# main.net
KiCad netlist of a schematic drawn in Altium Designer
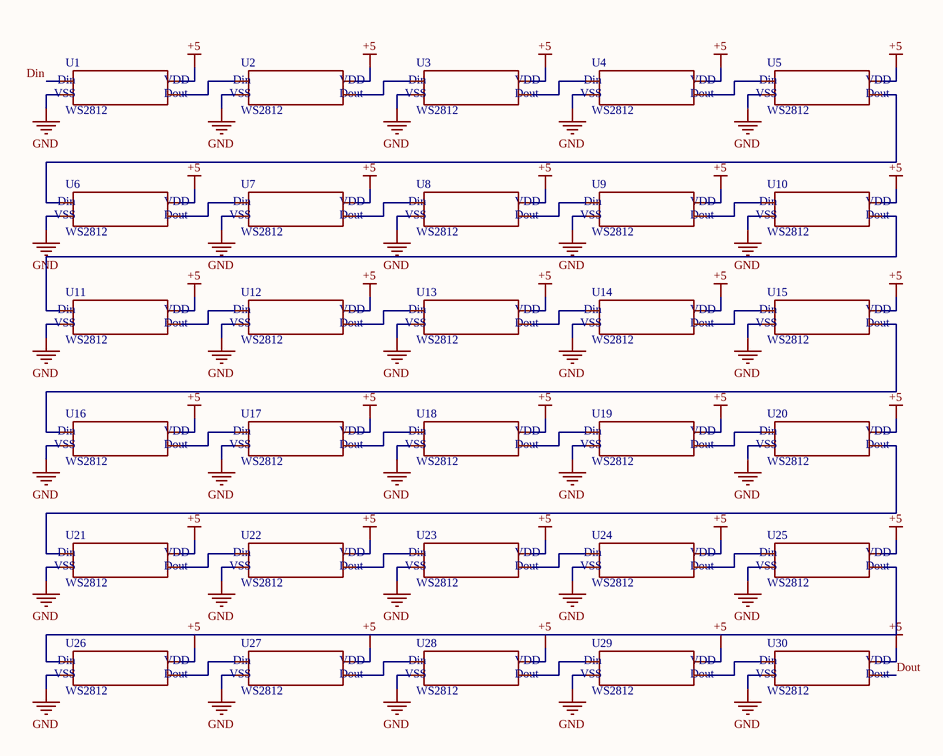
[diagram p0: main.SchDoc]

(export (version "E")
  (design (tool "Eeschema 10.0.6"))
  (components
    (comp (ref "U1") (value "WS2812") (footprint "3535") (libsource (lib "元件库") (part "芯片/IC-WS2812")))
    (comp (ref "U2") (value "WS2812") (footprint "3535") (libsource (lib "元件库") (part "芯片/IC-WS2812")))
    (comp (ref "U3") (value "WS2812") (footprint "3535") (libsource (lib "元件库") (part "芯片/IC-WS2812")))
    (comp (ref "U4") (value "WS2812") (footprint "3535") (libsource (lib "元件库") (part "芯片/IC-WS2812")))
    (comp (ref "U5") (value "WS2812") (footprint "3535") (libsource (lib "元件库") (part "芯片/IC-WS2812")))
    (comp (ref "U6") (value "WS2812") (footprint "3535") (libsource (lib "元件库") (part "芯片/IC-WS2812")))
    (comp (ref "U7") (value "WS2812") (footprint "3535") (libsource (lib "元件库") (part "芯片/IC-WS2812")))
    (comp (ref "U8") (value "WS2812") (footprint "3535") (libsource (lib "元件库") (part "芯片/IC-WS2812")))
    (comp (ref "U9") (value "WS2812") (footprint "3535") (libsource (lib "元件库") (part "芯片/IC-WS2812")))
    (comp (ref "U10") (value "WS2812") (footprint "3535") (libsource (lib "元件库") (part "芯片/IC-WS2812")))
    (comp (ref "U11") (value "WS2812") (footprint "3535") (libsource (lib "元件库") (part "芯片/IC-WS2812")))
    (comp (ref "U12") (value "WS2812") (footprint "3535") (libsource (lib "元件库") (part "芯片/IC-WS2812")))
    (comp (ref "U13") (value "WS2812") (footprint "3535") (libsource (lib "元件库") (part "芯片/IC-WS2812")))
    (comp (ref "U14") (value "WS2812") (footprint "3535") (libsource (lib "元件库") (part "芯片/IC-WS2812")))
    (comp (ref "U15") (value "WS2812") (footprint "3535") (libsource (lib "元件库") (part "芯片/IC-WS2812")))
    (comp (ref "U16") (value "WS2812") (footprint "3535") (libsource (lib "元件库") (part "芯片/IC-WS2812")))
    (comp (ref "U17") (value "WS2812") (footprint "3535") (libsource (lib "元件库") (part "芯片/IC-WS2812")))
    (comp (ref "U18") (value "WS2812") (footprint "3535") (libsource (lib "元件库") (part "芯片/IC-WS2812")))
    (comp (ref "U19") (value "WS2812") (footprint "3535") (libsource (lib "元件库") (part "芯片/IC-WS2812")))
    (comp (ref "U20") (value "WS2812") (footprint "3535") (libsource (lib "元件库") (part "芯片/IC-WS2812")))
    (comp (ref "U21") (value "WS2812") (footprint "3535") (libsource (lib "元件库") (part "芯片/IC-WS2812")))
    (comp (ref "U22") (value "WS2812") (footprint "3535") (libsource (lib "元件库") (part "芯片/IC-WS2812")))
    (comp (ref "U23") (value "WS2812") (footprint "3535") (libsource (lib "元件库") (part "芯片/IC-WS2812")))
    (comp (ref "U24") (value "WS2812") (footprint "3535") (libsource (lib "元件库") (part "芯片/IC-WS2812")))
    (comp (ref "U25") (value "WS2812") (footprint "3535") (libsource (lib "元件库") (part "芯片/IC-WS2812")))
    (comp (ref "U26") (value "WS2812") (footprint "3535") (libsource (lib "元件库") (part "芯片/IC-WS2812")))
    (comp (ref "U27") (value "WS2812") (footprint "3535") (libsource (lib "元件库") (part "芯片/IC-WS2812")))
    (comp (ref "U28") (value "WS2812") (footprint "3535") (libsource (lib "元件库") (part "芯片/IC-WS2812")))
    (comp (ref "U29") (value "WS2812") (footprint "3535") (libsource (lib "元件库") (part "芯片/IC-WS2812")))
    (comp (ref "U30") (value "WS2812") (footprint "3535") (libsource (lib "元件库") (part "芯片/IC-WS2812")))
  )
  (nets
    (net (code "1") (name "+5") (class "Default")
      (node (ref "U1") (pin "1") (pinfunction "1_1") (pintype "passive"))
      (node (ref "U10") (pin "1") (pinfunction "1_1") (pintype "passive"))
      (node (ref "U11") (pin "1") (pinfunction "1_1") (pintype "passive"))
      (node (ref "U12") (pin "1") (pinfunction "1_1") (pintype "passive"))
      (node (ref "U13") (pin "1") (pinfunction "1_1") (pintype "passive"))
      (node (ref "U14") (pin "1") (pinfunction "1_1") (pintype "passive"))
      (node (ref "U15") (pin "1") (pinfunction "1_1") (pintype "passive"))
      (node (ref "U16") (pin "1") (pinfunction "1_1") (pintype "passive"))
      (node (ref "U17") (pin "1") (pinfunction "1_1") (pintype "passive"))
      (node (ref "U18") (pin "1") (pinfunction "1_1") (pintype "passive"))
      (node (ref "U19") (pin "1") (pinfunction "1_1") (pintype "passive"))
      (node (ref "U2") (pin "1") (pinfunction "1_1") (pintype "passive"))
      (node (ref "U20") (pin "1") (pinfunction "1_1") (pintype "passive"))
      (node (ref "U21") (pin "1") (pinfunction "1_1") (pintype "passive"))
      (node (ref "U22") (pin "1") (pinfunction "1_1") (pintype "passive"))
      (node (ref "U23") (pin "1") (pinfunction "1_1") (pintype "passive"))
      (node (ref "U24") (pin "1") (pinfunction "1_1") (pintype "passive"))
      (node (ref "U25") (pin "1") (pinfunction "1_1") (pintype "passive"))
      (node (ref "U26") (pin "1") (pinfunction "1_1") (pintype "passive"))
      (node (ref "U27") (pin "1") (pinfunction "1_1") (pintype "passive"))
      (node (ref "U28") (pin "1") (pinfunction "1_1") (pintype "passive"))
      (node (ref "U29") (pin "1") (pinfunction "1_1") (pintype "passive"))
      (node (ref "U3") (pin "1") (pinfunction "1_1") (pintype "passive"))
      (node (ref "U30") (pin "1") (pinfunction "1_1") (pintype "passive"))
      (node (ref "U4") (pin "1") (pinfunction "1_1") (pintype "passive"))
      (node (ref "U5") (pin "1") (pinfunction "1_1") (pintype "passive"))
      (node (ref "U6") (pin "1") (pinfunction "1_1") (pintype "passive"))
      (node (ref "U7") (pin "1") (pinfunction "1_1") (pintype "passive"))
      (node (ref "U8") (pin "1") (pinfunction "1_1") (pintype "passive"))
      (node (ref "U9") (pin "1") (pinfunction "1_1") (pintype "passive"))
    )
    (net (code "2") (name "/Din") (class "Default")
      (node (ref "U1") (pin "4") (pinfunction "4_4") (pintype "passive"))
    )
    (net (code "3") (name "/Dout") (class "Default")
      (node (ref "U30") (pin "2") (pinfunction "2_2") (pintype "passive"))
    )
    (net (code "4") (name "GND") (class "Default")
      (node (ref "U1") (pin "3") (pinfunction "3_3") (pintype "passive"))
      (node (ref "U10") (pin "3") (pinfunction "3_3") (pintype "passive"))
      (node (ref "U11") (pin "3") (pinfunction "3_3") (pintype "passive"))
      (node (ref "U12") (pin "3") (pinfunction "3_3") (pintype "passive"))
      (node (ref "U13") (pin "3") (pinfunction "3_3") (pintype "passive"))
      (node (ref "U14") (pin "3") (pinfunction "3_3") (pintype "passive"))
      (node (ref "U15") (pin "3") (pinfunction "3_3") (pintype "passive"))
      (node (ref "U16") (pin "3") (pinfunction "3_3") (pintype "passive"))
      (node (ref "U17") (pin "3") (pinfunction "3_3") (pintype "passive"))
      (node (ref "U18") (pin "3") (pinfunction "3_3") (pintype "passive"))
      (node (ref "U19") (pin "3") (pinfunction "3_3") (pintype "passive"))
      (node (ref "U2") (pin "3") (pinfunction "3_3") (pintype "passive"))
      (node (ref "U20") (pin "3") (pinfunction "3_3") (pintype "passive"))
      (node (ref "U21") (pin "3") (pinfunction "3_3") (pintype "passive"))
      (node (ref "U22") (pin "3") (pinfunction "3_3") (pintype "passive"))
      (node (ref "U23") (pin "3") (pinfunction "3_3") (pintype "passive"))
      (node (ref "U24") (pin "3") (pinfunction "3_3") (pintype "passive"))
      (node (ref "U25") (pin "3") (pinfunction "3_3") (pintype "passive"))
      (node (ref "U26") (pin "3") (pinfunction "3_3") (pintype "passive"))
      (node (ref "U27") (pin "3") (pinfunction "3_3") (pintype "passive"))
      (node (ref "U28") (pin "3") (pinfunction "3_3") (pintype "passive"))
      (node (ref "U29") (pin "3") (pinfunction "3_3") (pintype "passive"))
      (node (ref "U3") (pin "3") (pinfunction "3_3") (pintype "passive"))
      (node (ref "U30") (pin "3") (pinfunction "3_3") (pintype "passive"))
      (node (ref "U4") (pin "3") (pinfunction "3_3") (pintype "passive"))
      (node (ref "U5") (pin "3") (pinfunction "3_3") (pintype "passive"))
      (node (ref "U6") (pin "3") (pinfunction "3_3") (pintype "passive"))
      (node (ref "U7") (pin "3") (pinfunction "3_3") (pintype "passive"))
      (node (ref "U8") (pin "3") (pinfunction "3_3") (pintype "passive"))
      (node (ref "U9") (pin "3") (pinfunction "3_3") (pintype "passive"))
    )
    (net (code "5") (name "Net-(U1-Pad2)") (class "Default")
      (node (ref "U1") (pin "2") (pinfunction "2_2") (pintype "passive"))
      (node (ref "U2") (pin "4") (pinfunction "4_4") (pintype "passive"))
    )
    (net (code "6") (name "Net-(U2-Pad2)") (class "Default")
      (node (ref "U2") (pin "2") (pinfunction "2_2") (pintype "passive"))
      (node (ref "U3") (pin "4") (pinfunction "4_4") (pintype "passive"))
    )
    (net (code "7") (name "Net-(U3-Pad2)") (class "Default")
      (node (ref "U3") (pin "2") (pinfunction "2_2") (pintype "passive"))
      (node (ref "U4") (pin "4") (pinfunction "4_4") (pintype "passive"))
    )
    (net (code "8") (name "Net-(U4-Pad2)") (class "Default")
      (node (ref "U4") (pin "2") (pinfunction "2_2") (pintype "passive"))
      (node (ref "U5") (pin "4") (pinfunction "4_4") (pintype "passive"))
    )
    (net (code "9") (name "Net-(U5-Pad2)") (class "Default")
      (node (ref "U5") (pin "2") (pinfunction "2_2") (pintype "passive"))
      (node (ref "U6") (pin "4") (pinfunction "4_4") (pintype "passive"))
    )
    (net (code "10") (name "Net-(U6-Pad2)") (class "Default")
      (node (ref "U6") (pin "2") (pinfunction "2_2") (pintype "passive"))
      (node (ref "U7") (pin "4") (pinfunction "4_4") (pintype "passive"))
    )
    (net (code "11") (name "Net-(U7-Pad2)") (class "Default")
      (node (ref "U7") (pin "2") (pinfunction "2_2") (pintype "passive"))
      (node (ref "U8") (pin "4") (pinfunction "4_4") (pintype "passive"))
    )
    (net (code "12") (name "Net-(U8-Pad2)") (class "Default")
      (node (ref "U8") (pin "2") (pinfunction "2_2") (pintype "passive"))
      (node (ref "U9") (pin "4") (pinfunction "4_4") (pintype "passive"))
    )
    (net (code "13") (name "Net-(U10-Pad2)") (class "Default")
      (node (ref "U10") (pin "2") (pinfunction "2_2") (pintype "passive"))
      (node (ref "U11") (pin "4") (pinfunction "4_4") (pintype "passive"))
    )
    (net (code "14") (name "Net-(U10-Pad4)") (class "Default")
      (node (ref "U10") (pin "4") (pinfunction "4_4") (pintype "passive"))
      (node (ref "U9") (pin "2") (pinfunction "2_2") (pintype "passive"))
    )
    (net (code "15") (name "Net-(U11-Pad2)") (class "Default")
      (node (ref "U11") (pin "2") (pinfunction "2_2") (pintype "passive"))
      (node (ref "U12") (pin "4") (pinfunction "4_4") (pintype "passive"))
    )
    (net (code "16") (name "Net-(U12-Pad2)") (class "Default")
      (node (ref "U12") (pin "2") (pinfunction "2_2") (pintype "passive"))
      (node (ref "U13") (pin "4") (pinfunction "4_4") (pintype "passive"))
    )
    (net (code "17") (name "Net-(U13-Pad2)") (class "Default")
      (node (ref "U13") (pin "2") (pinfunction "2_2") (pintype "passive"))
      (node (ref "U14") (pin "4") (pinfunction "4_4") (pintype "passive"))
    )
    (net (code "18") (name "Net-(U14-Pad2)") (class "Default")
      (node (ref "U14") (pin "2") (pinfunction "2_2") (pintype "passive"))
      (node (ref "U15") (pin "4") (pinfunction "4_4") (pintype "passive"))
    )
    (net (code "19") (name "Net-(U15-Pad2)") (class "Default")
      (node (ref "U15") (pin "2") (pinfunction "2_2") (pintype "passive"))
      (node (ref "U16") (pin "4") (pinfunction "4_4") (pintype "passive"))
    )
    (net (code "20") (name "Net-(U16-Pad2)") (class "Default")
      (node (ref "U16") (pin "2") (pinfunction "2_2") (pintype "passive"))
      (node (ref "U17") (pin "4") (pinfunction "4_4") (pintype "passive"))
    )
    (net (code "21") (name "Net-(U17-Pad2)") (class "Default")
      (node (ref "U17") (pin "2") (pinfunction "2_2") (pintype "passive"))
      (node (ref "U18") (pin "4") (pinfunction "4_4") (pintype "passive"))
    )
    (net (code "22") (name "Net-(U18-Pad2)") (class "Default")
      (node (ref "U18") (pin "2") (pinfunction "2_2") (pintype "passive"))
      (node (ref "U19") (pin "4") (pinfunction "4_4") (pintype "passive"))
    )
    (net (code "23") (name "Net-(U19-Pad2)") (class "Default")
      (node (ref "U19") (pin "2") (pinfunction "2_2") (pintype "passive"))
      (node (ref "U20") (pin "4") (pinfunction "4_4") (pintype "passive"))
    )
    (net (code "24") (name "Net-(U20-Pad2)") (class "Default")
      (node (ref "U20") (pin "2") (pinfunction "2_2") (pintype "passive"))
      (node (ref "U21") (pin "4") (pinfunction "4_4") (pintype "passive"))
    )
    (net (code "25") (name "Net-(U21-Pad2)") (class "Default")
      (node (ref "U21") (pin "2") (pinfunction "2_2") (pintype "passive"))
      (node (ref "U22") (pin "4") (pinfunction "4_4") (pintype "passive"))
    )
    (net (code "26") (name "Net-(U22-Pad2)") (class "Default")
      (node (ref "U22") (pin "2") (pinfunction "2_2") (pintype "passive"))
      (node (ref "U23") (pin "4") (pinfunction "4_4") (pintype "passive"))
    )
    (net (code "27") (name "Net-(U23-Pad2)") (class "Default")
      (node (ref "U23") (pin "2") (pinfunction "2_2") (pintype "passive"))
      (node (ref "U24") (pin "4") (pinfunction "4_4") (pintype "passive"))
    )
    (net (code "28") (name "Net-(U24-Pad2)") (class "Default")
      (node (ref "U24") (pin "2") (pinfunction "2_2") (pintype "passive"))
      (node (ref "U25") (pin "4") (pinfunction "4_4") (pintype "passive"))
    )
    (net (code "29") (name "Net-(U25-Pad2)") (class "Default")
      (node (ref "U25") (pin "2") (pinfunction "2_2") (pintype "passive"))
      (node (ref "U26") (pin "4") (pinfunction "4_4") (pintype "passive"))
    )
    (net (code "30") (name "Net-(U26-Pad2)") (class "Default")
      (node (ref "U26") (pin "2") (pinfunction "2_2") (pintype "passive"))
      (node (ref "U27") (pin "4") (pinfunction "4_4") (pintype "passive"))
    )
    (net (code "31") (name "Net-(U27-Pad2)") (class "Default")
      (node (ref "U27") (pin "2") (pinfunction "2_2") (pintype "passive"))
      (node (ref "U28") (pin "4") (pinfunction "4_4") (pintype "passive"))
    )
    (net (code "32") (name "Net-(U28-Pad2)") (class "Default")
      (node (ref "U28") (pin "2") (pinfunction "2_2") (pintype "passive"))
      (node (ref "U29") (pin "4") (pinfunction "4_4") (pintype "passive"))
    )
    (net (code "33") (name "Net-(U29-Pad2)") (class "Default")
      (node (ref "U29") (pin "2") (pinfunction "2_2") (pintype "passive"))
      (node (ref "U30") (pin "4") (pinfunction "4_4") (pintype "passive"))
    )
  )
)
